# Sketch.net
KiCad netlist of a schematic drawn in EasyEDA
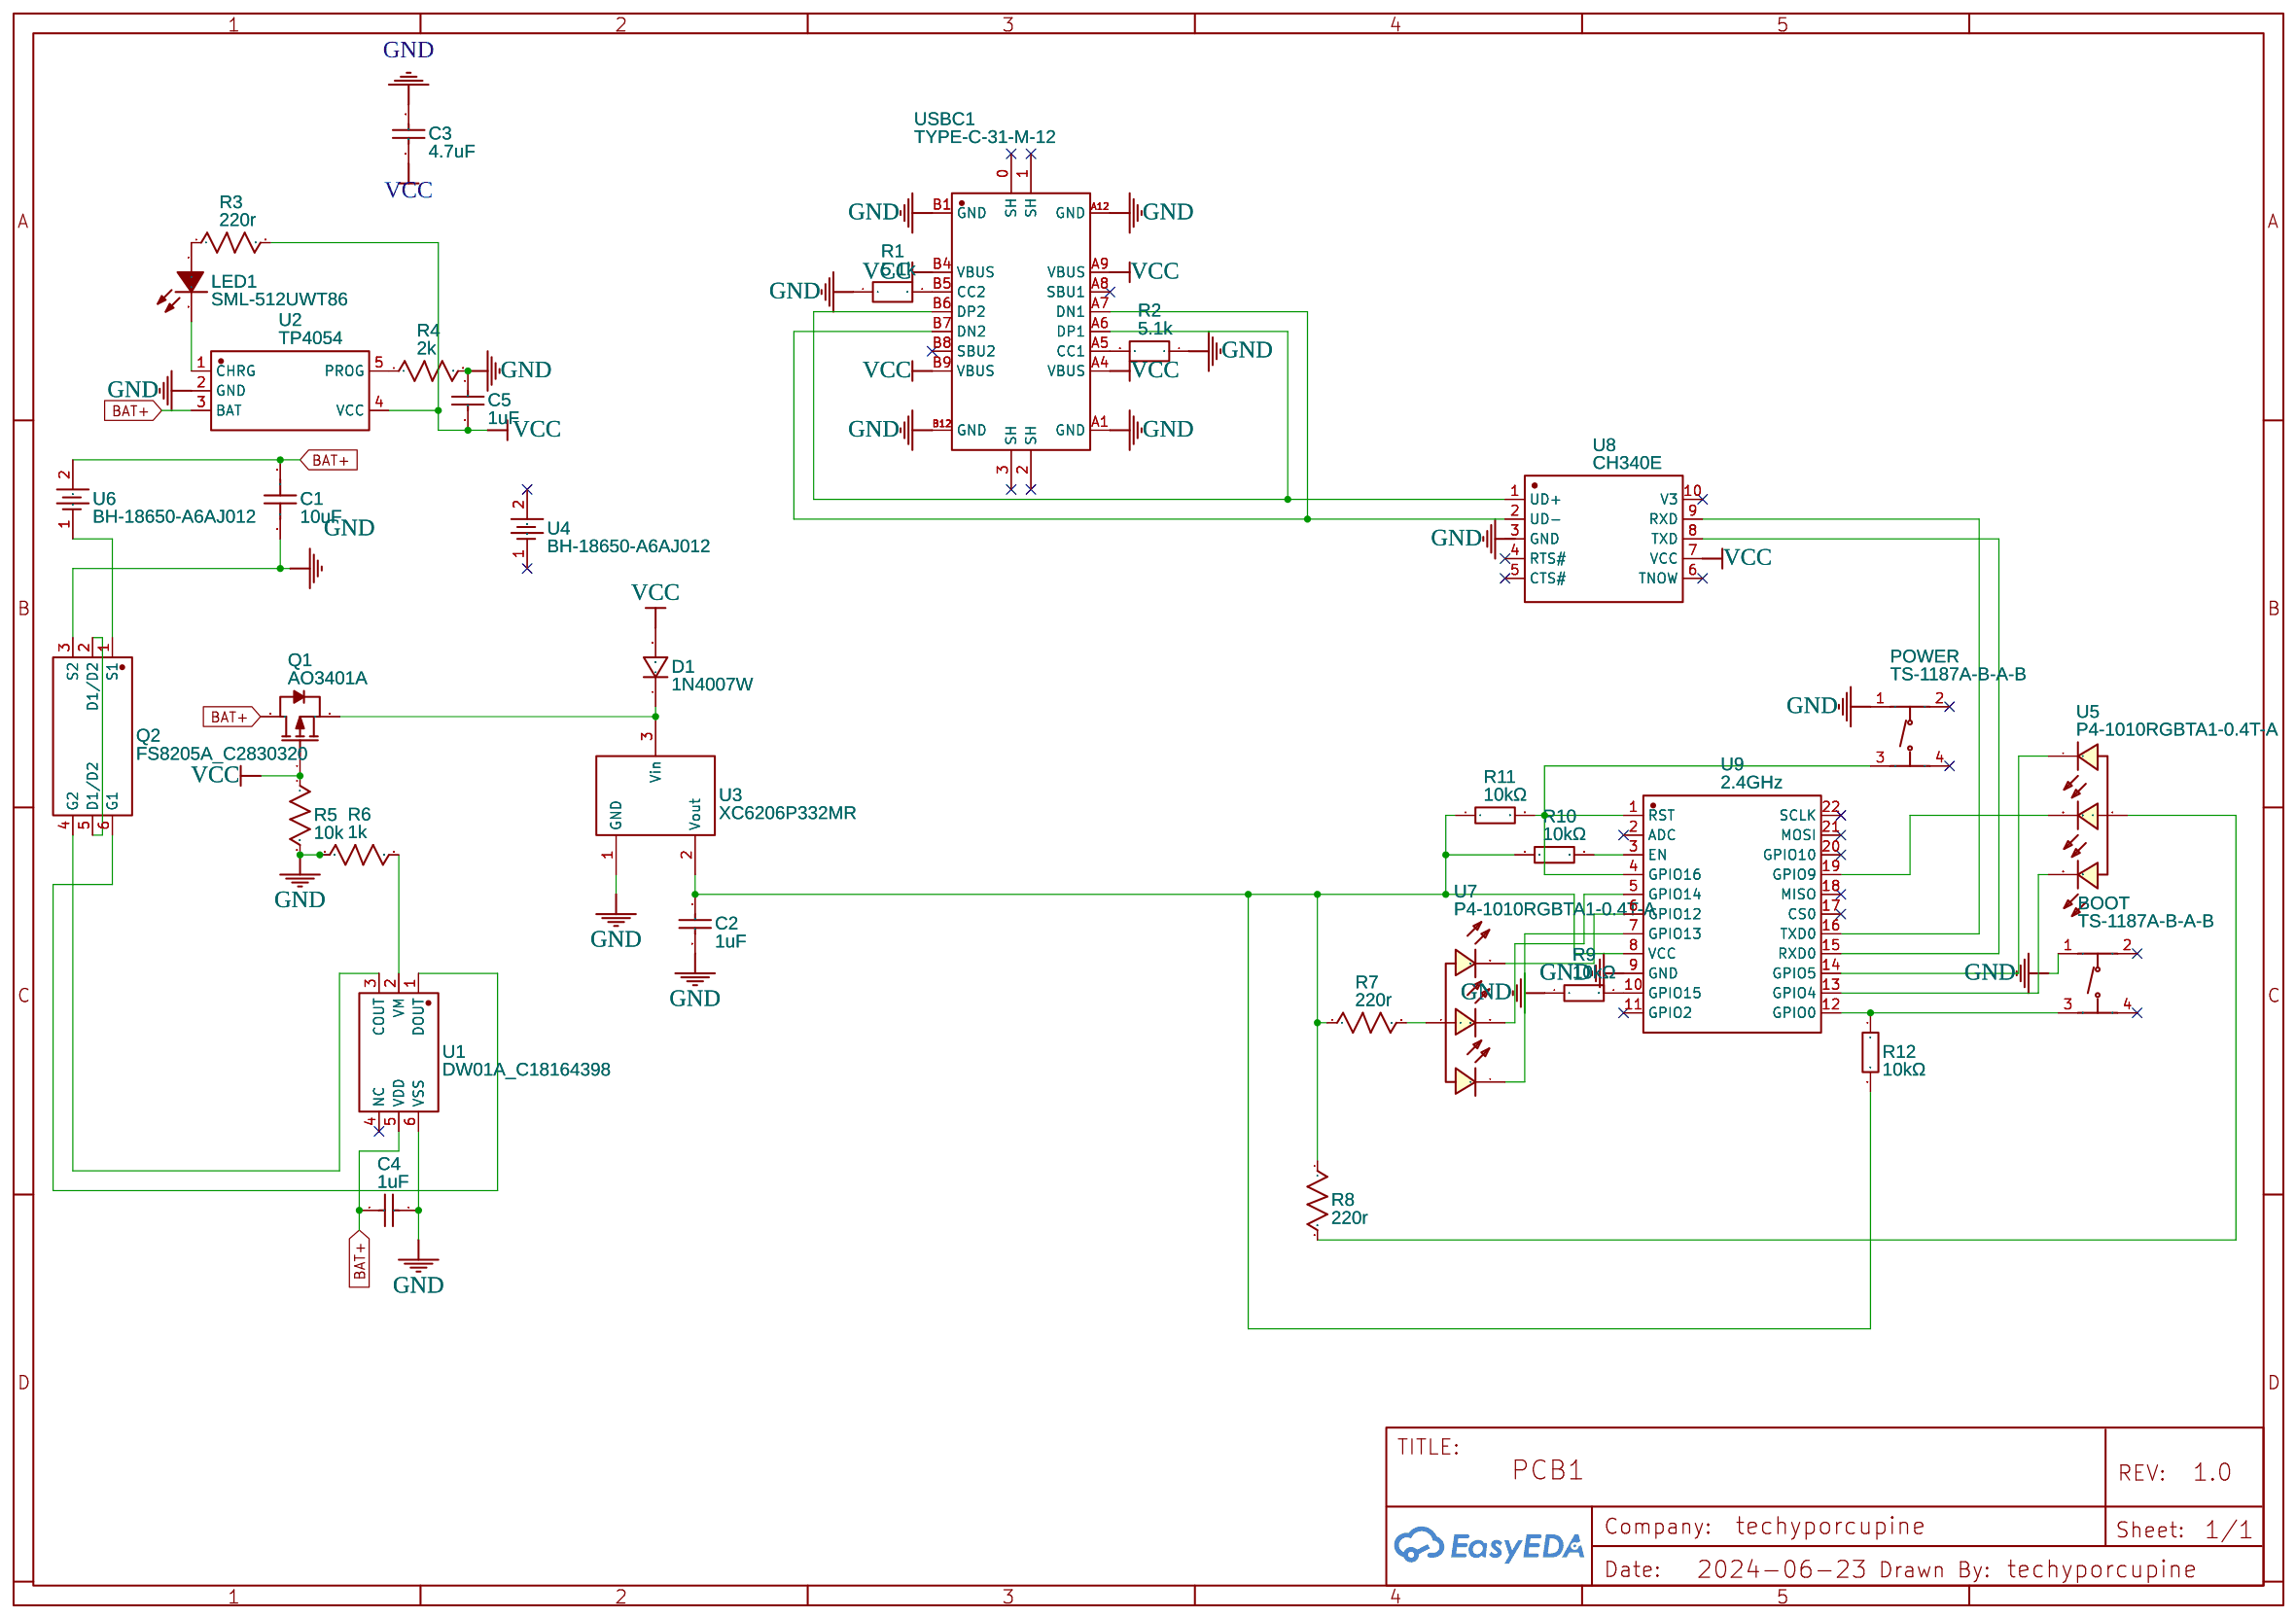
[diagram p0: schematic sheet]

(export (version "E")
  (design (tool "Eeschema 10.0.6"))
  (components
    (comp (ref "BOOT")
      (value "TS-1187A-B-A-B")
      (fields (field (name "Manufacturer") "XKB Connectivity(中国星坤)"))
      (libsource (lib "") (part "TS-1187A-B-A-B"))
    )
    (comp (ref "C1")
      (value "10uF")
      (fields
        (field (name "Manufacturer Part") "GRT21BC71E106KE13L")
        (field (name "Manufacturer") "muRata(村田)")
      )
      (libsource (lib "") (part "GRT21BC71E106KE13L"))
    )
    (comp (ref "C2")
      (value "1uF")
      (fields (field (name "Manufacturer Part") "0805F105M500NT") (field (name "Manufacturer") "FH(风华)"))
      (libsource (lib "") (part "0805F105M500NT"))
    )
    (comp (ref "C3")
      (value "4.7uF")
      (fields
        (field (name "Manufacturer Part") "CL21A475KAQNNNE")
        (field (name "Manufacturer") "SAMSUNG(三星)")
      )
      (libsource (lib "") (part "CL21A475KAQNNNE"))
    )
    (comp (ref "C4")
      (value "1uF")
      (fields (field (name "Manufacturer Part") "0805F105M500NT") (field (name "Manufacturer") "FH(风华)"))
      (libsource (lib "") (part "0805F105M500NT_1"))
    )
    (comp (ref "C5")
      (value "1uF")
      (fields (field (name "Manufacturer Part") "0805F105M500NT") (field (name "Manufacturer") "FH(风华)"))
      (libsource (lib "") (part "0805F105M500NT"))
    )
    (comp (ref "D1")
      (value "1N4007W")
      (fields (field (name "Manufacturer") "BLUE ROCKET"))
      (libsource (lib "") (part "1N4007W"))
    )
    (comp (ref "LED1")
      (value "SML-512UWT86")
      (fields (field (name "Manufacturer Part") "SML-D12M1WT86") (field (name "Manufacturer") "ROHM(罗姆)"))
      (libsource (lib "") (part "SML-512UWT86"))
    )
    (comp (ref "POWER")
      (value "TS-1187A-B-A-B")
      (fields (field (name "Manufacturer") "XKB Connectivity(中国星坤)"))
      (libsource (lib "") (part "TS-1187A-B-A-B_1"))
    )
    (comp (ref "Q1")
      (value "AO3401A")
      (fields (field (name "Manufacturer") "AOS"))
      (libsource (lib "") (part "AO3401A"))
    )
    (comp (ref "Q2")
      (value "FS8205A_C2830320")
      (fields (field (name "Manufacturer Part") "FS8205A") (field (name "Manufacturer") "TECH PUBLIC(台舟)"))
      (libsource (lib "") (part "FS8205A_C2830320"))
    )
    (comp (ref "R1")
      (value "5.1k")
      (fields (field (name "Manufacturer Part") "RTT015101FTH") (field (name "Manufacturer") "RALEC(旺诠)"))
      (libsource (lib "") (part "R_0603_EU_1"))
    )
    (comp (ref "R2")
      (value "5.1k")
      (fields (field (name "Manufacturer Part") "RTT015101FTH") (field (name "Manufacturer") "RALEC(旺诠)"))
      (libsource (lib "") (part "R_0603_EU"))
    )
    (comp (ref "R3")
      (value "220r")
      (fields
        (field (name "Manufacturer Part") "0603WAF2200T5E")
        (field (name "Manufacturer") "UNI-ROYAL(厚声)")
      )
      (libsource (lib "") (part "R_0603_US_1"))
    )
    (comp (ref "R4")
      (value "2k")
      (fields
        (field (name "Manufacturer Part") "0402WGF2001TCE")
        (field (name "Manufacturer") "UNI-ROYAL(厚声)")
      )
      (libsource (lib "") (part "R_0603_US_1"))
    )
    (comp (ref "R5")
      (value "10k")
      (fields (field (name "Manufacturer Part") "ARG02BTC1002") (field (name "Manufacturer") "Viking(光颉)"))
      (libsource (lib "") (part "R_0603_US"))
    )
    (comp (ref "R6")
      (value "1k")
      (fields
        (field (name "Manufacturer Part") "0805W8F1001T5E")
        (field (name "Manufacturer") "UNI-ROYAL(厚声)")
      )
      (libsource (lib "") (part "R_0603_US_1"))
    )
    (comp (ref "R7")
      (value "220r")
      (fields
        (field (name "Manufacturer Part") "0603WAF2200T5E")
        (field (name "Manufacturer") "UNI-ROYAL(厚声)")
      )
      (libsource (lib "") (part "R_0603_US_1"))
    )
    (comp (ref "R8")
      (value "220r")
      (fields
        (field (name "Manufacturer Part") "0603WAF2200T5E")
        (field (name "Manufacturer") "UNI-ROYAL(厚声)")
      )
      (libsource (lib "") (part "R_0603_US"))
    )
    (comp (ref "R9")
      (value "10kΩ")
      (fields
        (field (name "Manufacturer Part") "0603WAF1002T5E")
        (field (name "Manufacturer") "UNI-ROYAL(厚声)")
      )
      (libsource (lib "") (part "0603WAF1002T5E"))
    )
    (comp (ref "R10")
      (value "10kΩ")
      (fields
        (field (name "Manufacturer Part") "0603WAF1002T5E")
        (field (name "Manufacturer") "UNI-ROYAL(厚声)")
      )
      (libsource (lib "") (part "0603WAF1002T5E"))
    )
    (comp (ref "R11")
      (value "10kΩ")
      (fields
        (field (name "Manufacturer Part") "0603WAF1002T5E")
        (field (name "Manufacturer") "UNI-ROYAL(厚声)")
      )
      (libsource (lib "") (part "0603WAF1002T5E"))
    )
    (comp (ref "R12")
      (value "10kΩ")
      (fields
        (field (name "Manufacturer Part") "0603WAF1002T5E")
        (field (name "Manufacturer") "UNI-ROYAL(厚声)")
      )
      (libsource (lib "") (part "0603WAF1002T5E_1"))
    )
    (comp (ref "U1")
      (value "DW01A_C18164398")
      (fields (field (name "Manufacturer Part") "DW01A") (field (name "Manufacturer") "HL(富海微)"))
      (libsource (lib "") (part "DW01A_C18164398"))
    )
    (comp (ref "U2")
      (value "TP4054")
      (fields
        (field (name "Manufacturer Part") "TP4054-42-SOT25R")
        (field (name "Manufacturer") "TOPPOWER(南京拓微)")
      )
      (libsource (lib "") (part "TP4054"))
    )
    (comp (ref "U3")
      (value "XC6206P332MR")
      (fields (field (name "Manufacturer Part") "XC6206P332MR-G") (field (name "Manufacturer") "TOREX(特瑞仕)"))
      (libsource (lib "") (part "XC6206P332MR"))
    )
    (comp (ref "U4")
      (value "BH-18650-A6AJ012")
      (fields (field (name "Manufacturer") "MYOUNG(美阳)"))
      (libsource (lib "") (part "BH-18650-A6AJ012"))
    )
    (comp (ref "U5")
      (value "P4-1010RGBTA1-0.4T-A")
      (fields (field (name "Manufacturer") "TUOZHAN(拓展光电)"))
      (libsource (lib "") (part "P4-1010RGBTA1-0.4T-A_1"))
    )
    (comp (ref "U6")
      (value "BH-18650-A6AJ012")
      (fields (field (name "Manufacturer") "MYOUNG(美阳)"))
      (libsource (lib "") (part "BH-18650-A6AJ012"))
    )
    (comp (ref "U7")
      (value "P4-1010RGBTA1-0.4T-A")
      (fields (field (name "Manufacturer") "TUOZHAN(拓展光电)"))
      (libsource (lib "") (part "P4-1010RGBTA1-0.4T-A"))
    )
    (comp (ref "U8")
      (value "CH340E")
      (fields (field (name "Manufacturer") "WCH(南京沁恒)"))
      (libsource (lib "") (part "CH340E"))
    )
    (comp (ref "U9")
      (value "2.4GHz")
      (fields
        (field (name "Manufacturer Part") "ESP-12F(ESP8266MOD)")
        (field (name "Manufacturer") "Ai-Thinker(安信可)")
      )
      (libsource (lib "") (part "ESP-12F(ESP8266MOD)"))
    )
    (comp (ref "USBC1")
      (value "TYPE-C-31-M-12")
      (fields (field (name "Manufacturer") "韩国韩荣"))
      (libsource (lib "") (part "TYPE-C-31-M-12"))
    )
  )
  (nets
    (net (code "1") (name "BAT+") (class "Default")
      (node (ref "C1") (pin "2") (pinfunction "2_2") (pintype "unspecified"))
      (node (ref "C4") (pin "2") (pinfunction "2_2") (pintype "input"))
      (node (ref "Q1") (pin "3") (pinfunction "D_3") (pintype "unspecified"))
      (node (ref "U1") (pin "5") (pinfunction "VDD_5") (pintype "unspecified"))
      (node (ref "U2") (pin "3") (pinfunction "BAT_3") (pintype "unspecified"))
      (node (ref "U6") (pin "2") (pinfunction "2_2") (pintype "input"))
    )
    (net (code "2") (name "GND") (class "Default")
      (node (ref "BOOT") (pin "1") (pinfunction "A_1") (pintype "unspecified"))
      (node (ref "C1") (pin "1") (pinfunction "1_1") (pintype "unspecified"))
      (node (ref "C2") (pin "2") (pinfunction "2_2") (pintype "input"))
      (node (ref "C3") (pin "2") (pinfunction "2_2") (pintype "input"))
      (node (ref "C4") (pin "1") (pinfunction "1_1") (pintype "input"))
      (node (ref "C5") (pin "1") (pinfunction "1_1") (pintype "input"))
      (node (ref "POWER") (pin "1") (pinfunction "A_1") (pintype "unspecified"))
      (node (ref "Q2") (pin "3") (pinfunction "S2_3") (pintype "unspecified"))
      (node (ref "R1") (pin "1") (pinfunction "1_1") (pintype "unspecified"))
      (node (ref "R2") (pin "1") (pinfunction "1_1") (pintype "unspecified"))
      (node (ref "R4") (pin "2") (pinfunction "2_2") (pintype "unspecified"))
      (node (ref "R5") (pin "2") (pinfunction "2_2") (pintype "unspecified"))
      (node (ref "R6") (pin "1") (pinfunction "1_1") (pintype "unspecified"))
      (node (ref "R9") (pin "1") (pinfunction "1_1") (pintype "input"))
      (node (ref "U1") (pin "6") (pinfunction "VSS_6") (pintype "unspecified"))
      (node (ref "U2") (pin "2") (pinfunction "GND_2") (pintype "unspecified"))
      (node (ref "U3") (pin "1") (pinfunction "GND_1") (pintype "unspecified"))
      (node (ref "U8") (pin "3") (pinfunction "GND_3") (pintype "unspecified"))
      (node (ref "U9") (pin "9") (pinfunction "GND_9") (pintype "unspecified"))
      (node (ref "USBC1") (pin "A1") (pinfunction "GND_A1") (pintype "unspecified"))
      (node (ref "USBC1") (pin "A12") (pinfunction "GND_A12") (pintype "unspecified"))
      (node (ref "USBC1") (pin "B1") (pinfunction "GND_B1") (pintype "unspecified"))
      (node (ref "USBC1") (pin "B12") (pinfunction "GND_B12") (pintype "unspecified"))
    )
    (net (code "3") (name "Net-(BOOT-C)") (class "Default")
      (node (ref "BOOT") (pin "3") (pinfunction "C_3") (pintype "unspecified"))
      (node (ref "R12") (pin "1") (pinfunction "1_1") (pintype "input"))
      (node (ref "U9") (pin "12") (pinfunction "GPIO0_12") (pintype "unspecified"))
    )
    (net (code "4") (name "Net-(LED1-A)") (class "Default")
      (node (ref "LED1") (pin "1") (pinfunction "A_1") (pintype "unspecified"))
      (node (ref "R3") (pin "1") (pinfunction "1_1") (pintype "unspecified"))
    )
    (net (code "5") (name "Net-(LED1-K)") (class "Default")
      (node (ref "LED1") (pin "2") (pinfunction "K_2") (pintype "unspecified"))
      (node (ref "U2") (pin "1") (pinfunction "CHRG_1") (pintype "unspecified"))
    )
    (net (code "6") (name "Net-(POWER-C)") (class "Default")
      (node (ref "POWER") (pin "3") (pinfunction "C_3") (pintype "unspecified"))
      (node (ref "R11") (pin "2") (pinfunction "2_2") (pintype "input"))
      (node (ref "U9") (pin "1") (pinfunction "RST_1") (pintype "unspecified"))
      (node (ref "U9") (pin "4") (pinfunction "GPIO16_4") (pintype "unspecified"))
    )
    (net (code "7") (name "Net-(Q1-S)") (class "Default")
      (node (ref "D1") (pin "1") (pinfunction "1_1") (pintype "unspecified"))
      (node (ref "Q1") (pin "2") (pinfunction "S_2") (pintype "unspecified"))
      (node (ref "U3") (pin "3") (pinfunction "Vin_3") (pintype "unspecified"))
    )
    (net (code "8") (name "Net-(Q2-D1{slash}D2-Pad2)") (class "Default")
      (node (ref "Q2") (pin "2") (pinfunction "D1/D2_2") (pintype "unspecified"))
      (node (ref "Q2") (pin "5") (pinfunction "D1/D2_5") (pintype "unspecified"))
    )
    (net (code "9") (name "Net-(Q2-G1)") (class "Default")
      (node (ref "Q2") (pin "6") (pinfunction "G1_6") (pintype "unspecified"))
      (node (ref "U1") (pin "1") (pinfunction "DOUT_1") (pintype "unspecified"))
    )
    (net (code "10") (name "Net-(Q2-G2)") (class "Default")
      (node (ref "Q2") (pin "4") (pinfunction "G2_4") (pintype "unspecified"))
      (node (ref "U1") (pin "3") (pinfunction "COUT_3") (pintype "unspecified"))
    )
    (net (code "11") (name "Net-(Q2-S1)") (class "Default")
      (node (ref "Q2") (pin "1") (pinfunction "S1_1") (pintype "unspecified"))
      (node (ref "U6") (pin "1") (pinfunction "1_1") (pintype "input"))
    )
    (net (code "12") (name "Net-(R7-Pad2)") (class "Default")
      (node (ref "R7") (pin "2") (pinfunction "2_2") (pintype "unspecified"))
      (node (ref "U7") (pin "1") (pinfunction "1_1") (pintype "unspecified"))
    )
    (net (code "13") (name "Net-(R8-Pad2)") (class "Default")
      (node (ref "R8") (pin "2") (pinfunction "2_2") (pintype "unspecified"))
      (node (ref "U5") (pin "1") (pinfunction "1_1") (pintype "unspecified"))
    )
    (net (code "14") (name "Net-(U1-VM)") (class "Default")
      (node (ref "R6") (pin "2") (pinfunction "2_2") (pintype "unspecified"))
      (node (ref "U1") (pin "2") (pinfunction "VM_2") (pintype "unspecified"))
    )
    (net (code "15") (name "Net-(U2-PROG)") (class "Default")
      (node (ref "R4") (pin "1") (pinfunction "1_1") (pintype "unspecified"))
      (node (ref "U2") (pin "5") (pinfunction "PROG_5") (pintype "unspecified"))
    )
    (net (code "16") (name "Net-(U3-Vout)") (class "Default")
      (node (ref "C2") (pin "1") (pinfunction "1_1") (pintype "input"))
      (node (ref "R10") (pin "1") (pinfunction "1_1") (pintype "input"))
      (node (ref "R11") (pin "1") (pinfunction "1_1") (pintype "input"))
      (node (ref "R12") (pin "2") (pinfunction "2_2") (pintype "input"))
      (node (ref "R7") (pin "1") (pinfunction "1_1") (pintype "unspecified"))
      (node (ref "R8") (pin "1") (pinfunction "1_1") (pintype "unspecified"))
      (node (ref "U3") (pin "2") (pinfunction "Vout_2") (pintype "unspecified"))
      (node (ref "U9") (pin "8") (pinfunction "VCC_8") (pintype "unspecified"))
    )
    (net (code "17") (name "Net-(U8-RXD)") (class "Default")
      (node (ref "U8") (pin "9") (pinfunction "RXD_9") (pintype "unspecified"))
      (node (ref "U9") (pin "16") (pinfunction "TXD0_16") (pintype "unspecified"))
    )
    (net (code "18") (name "Net-(U8-TXD)") (class "Default")
      (node (ref "U8") (pin "8") (pinfunction "TXD_8") (pintype "unspecified"))
      (node (ref "U9") (pin "15") (pinfunction "RXD0_15") (pintype "unspecified"))
    )
    (net (code "19") (name "Net-(U8-UD+)") (class "Default")
      (node (ref "U8") (pin "1") (pinfunction "UD+_1") (pintype "unspecified"))
      (node (ref "USBC1") (pin "A6") (pinfunction "DP1_A6") (pintype "unspecified"))
      (node (ref "USBC1") (pin "B6") (pinfunction "DP2_B6") (pintype "unspecified"))
    )
    (net (code "20") (name "Net-(U8-UD-)") (class "Default")
      (node (ref "U8") (pin "2") (pinfunction "UD-_2") (pintype "unspecified"))
      (node (ref "USBC1") (pin "A7") (pinfunction "DN1_A7") (pintype "unspecified"))
      (node (ref "USBC1") (pin "B7") (pinfunction "DN2_B7") (pintype "unspecified"))
    )
    (net (code "21") (name "Net-(U9-EN)") (class "Default")
      (node (ref "R10") (pin "2") (pinfunction "2_2") (pintype "input"))
      (node (ref "U9") (pin "3") (pinfunction "EN_3") (pintype "unspecified"))
    )
    (net (code "22") (name "Net-(U9-GPIO4)") (class "Default")
      (node (ref "U5") (pin "2") (pinfunction "2_2") (pintype "unspecified"))
      (node (ref "U9") (pin "13") (pinfunction "GPIO4_13") (pintype "unspecified"))
    )
    (net (code "23") (name "Net-(U9-GPIO5)") (class "Default")
      (node (ref "U5") (pin "4") (pinfunction "4_4") (pintype "unspecified"))
      (node (ref "U9") (pin "14") (pinfunction "GPIO5_14") (pintype "unspecified"))
    )
    (net (code "24") (name "Net-(U9-GPIO9)") (class "Default")
      (node (ref "U5") (pin "3") (pinfunction "3_3") (pintype "unspecified"))
      (node (ref "U9") (pin "19") (pinfunction "GPIO9_19") (pintype "unspecified"))
    )
    (net (code "25") (name "Net-(U9-GPIO12)") (class "Default")
      (node (ref "U7") (pin "2") (pinfunction "2_2") (pintype "unspecified"))
      (node (ref "U9") (pin "6") (pinfunction "GPIO12_6") (pintype "unspecified"))
    )
    (net (code "26") (name "Net-(U9-GPIO13)") (class "Default")
      (node (ref "U7") (pin "4") (pinfunction "4_4") (pintype "unspecified"))
      (node (ref "U9") (pin "7") (pinfunction "GPIO13_7") (pintype "unspecified"))
    )
    (net (code "27") (name "Net-(U9-GPIO14)") (class "Default")
      (node (ref "U7") (pin "3") (pinfunction "3_3") (pintype "unspecified"))
      (node (ref "U9") (pin "5") (pinfunction "GPIO14_5") (pintype "unspecified"))
    )
    (net (code "28") (name "Net-(U9-GPIO15)") (class "Default")
      (node (ref "R9") (pin "2") (pinfunction "2_2") (pintype "input"))
      (node (ref "U9") (pin "10") (pinfunction "GPIO15_10") (pintype "unspecified"))
    )
    (net (code "29") (name "Net-(USBC1-CC1)") (class "Default")
      (node (ref "R2") (pin "2") (pinfunction "2_2") (pintype "unspecified"))
      (node (ref "USBC1") (pin "A5") (pinfunction "CC1_A5") (pintype "unspecified"))
    )
    (net (code "30") (name "Net-(USBC1-CC2)") (class "Default")
      (node (ref "R1") (pin "2") (pinfunction "2_2") (pintype "unspecified"))
      (node (ref "USBC1") (pin "B5") (pinfunction "CC2_B5") (pintype "unspecified"))
    )
    (net (code "31") (name "VCC") (class "Default")
      (node (ref "C3") (pin "1") (pinfunction "1_1") (pintype "input"))
      (node (ref "C5") (pin "2") (pinfunction "2_2") (pintype "input"))
      (node (ref "D1") (pin "2") (pinfunction "2_2") (pintype "unspecified"))
      (node (ref "Q1") (pin "1") (pinfunction "G_1") (pintype "unspecified"))
      (node (ref "R3") (pin "2") (pinfunction "2_2") (pintype "unspecified"))
      (node (ref "R5") (pin "1") (pinfunction "1_1") (pintype "unspecified"))
      (node (ref "U2") (pin "4") (pinfunction "VCC_4") (pintype "unspecified"))
      (node (ref "U8") (pin "7") (pinfunction "VCC_7") (pintype "unspecified"))
      (node (ref "USBC1") (pin "A4") (pinfunction "VBUS_A4") (pintype "unspecified"))
      (node (ref "USBC1") (pin "A9") (pinfunction "VBUS_A9") (pintype "unspecified"))
      (node (ref "USBC1") (pin "B4") (pinfunction "VBUS_B4") (pintype "unspecified"))
      (node (ref "USBC1") (pin "B9") (pinfunction "VBUS_B9") (pintype "unspecified"))
    )
    (net (code "32") (name "unconnected-(BOOT-B-Pad2)") (class "Default")
      (node (ref "BOOT") (pin "2") (pinfunction "B_2") (pintype "unspecified+no_connect"))
    )
    (net (code "33") (name "unconnected-(BOOT-D-Pad4)") (class "Default")
      (node (ref "BOOT") (pin "4") (pinfunction "D_4") (pintype "unspecified+no_connect"))
    )
    (net (code "34") (name "unconnected-(POWER-B-Pad2)") (class "Default")
      (node (ref "POWER") (pin "2") (pinfunction "B_2") (pintype "unspecified+no_connect"))
    )
    (net (code "35") (name "unconnected-(POWER-D-Pad4)") (class "Default")
      (node (ref "POWER") (pin "4") (pinfunction "D_4") (pintype "unspecified+no_connect"))
    )
    (net (code "36") (name "unconnected-(U1-NC-Pad4)") (class "Default")
      (node (ref "U1") (pin "4") (pinfunction "NC_4") (pintype "unspecified+no_connect"))
    )
    (net (code "37") (name "unconnected-(U4-Pad1)") (class "Default")
      (node (ref "U4") (pin "1") (pinfunction "1_1") (pintype "input+no_connect"))
    )
    (net (code "38") (name "unconnected-(U4-Pad2)") (class "Default")
      (node (ref "U4") (pin "2") (pinfunction "2_2") (pintype "input+no_connect"))
    )
    (net (code "39") (name "unconnected-(U8-CTS#-Pad5)") (class "Default")
      (node (ref "U8") (pin "5") (pinfunction "CTS#_5") (pintype "unspecified+no_connect"))
    )
    (net (code "40") (name "unconnected-(U8-RTS#-Pad4)") (class "Default")
      (node (ref "U8") (pin "4") (pinfunction "RTS#_4") (pintype "unspecified+no_connect"))
    )
    (net (code "41") (name "unconnected-(U8-TNOW-Pad6)") (class "Default")
      (node (ref "U8") (pin "6") (pinfunction "TNOW_6") (pintype "unspecified+no_connect"))
    )
    (net (code "42") (name "unconnected-(U8-V3-Pad10)") (class "Default")
      (node (ref "U8") (pin "10") (pinfunction "V3_10") (pintype "unspecified+no_connect"))
    )
    (net (code "43") (name "unconnected-(U9-ADC-Pad2)") (class "Default")
      (node (ref "U9") (pin "2") (pinfunction "ADC_2") (pintype "unspecified+no_connect"))
    )
    (net (code "44") (name "unconnected-(U9-CS0-Pad17)") (class "Default")
      (node (ref "U9") (pin "17") (pinfunction "CS0_17") (pintype "unspecified+no_connect"))
    )
    (net (code "45") (name "unconnected-(U9-GPIO2-Pad11)") (class "Default")
      (node (ref "U9") (pin "11") (pinfunction "GPIO2_11") (pintype "unspecified+no_connect"))
    )
    (net (code "46") (name "unconnected-(U9-GPIO10-Pad20)") (class "Default")
      (node (ref "U9") (pin "20") (pinfunction "GPIO10_20") (pintype "unspecified+no_connect"))
    )
    (net (code "47") (name "unconnected-(U9-MISO-Pad18)") (class "Default")
      (node (ref "U9") (pin "18") (pinfunction "MISO_18") (pintype "unspecified+no_connect"))
    )
    (net (code "48") (name "unconnected-(U9-MOSI-Pad21)") (class "Default")
      (node (ref "U9") (pin "21") (pinfunction "MOSI_21") (pintype "unspecified+no_connect"))
    )
    (net (code "49") (name "unconnected-(U9-SCLK-Pad22)") (class "Default")
      (node (ref "U9") (pin "22") (pinfunction "SCLK_22") (pintype "unspecified+no_connect"))
    )
    (net (code "50") (name "unconnected-(USBC1-SBU1-PadA8)") (class "Default")
      (node (ref "USBC1") (pin "A8") (pinfunction "SBU1_A8") (pintype "unspecified+no_connect"))
    )
    (net (code "51") (name "unconnected-(USBC1-SBU2-PadB8)") (class "Default")
      (node (ref "USBC1") (pin "B8") (pinfunction "SBU2_B8") (pintype "unspecified+no_connect"))
    )
    (net (code "52") (name "unconnected-(USBC1-SH-Pad0)") (class "Default")
      (node (ref "USBC1") (pin "0") (pinfunction "SH_0") (pintype "unspecified+no_connect"))
    )
    (net (code "53") (name "unconnected-(USBC1-SH-Pad1)") (class "Default")
      (node (ref "USBC1") (pin "1") (pinfunction "SH_1") (pintype "unspecified+no_connect"))
    )
    (net (code "54") (name "unconnected-(USBC1-SH-Pad2)") (class "Default")
      (node (ref "USBC1") (pin "2") (pinfunction "SH_2") (pintype "unspecified+no_connect"))
    )
    (net (code "55") (name "unconnected-(USBC1-SH-Pad3)") (class "Default")
      (node (ref "USBC1") (pin "3") (pinfunction "SH_3") (pintype "unspecified+no_connect"))
    )
  )
)
